# seeknobs5qtpy_22Feb2022.net
KiCad netlist of a schematic drawn in EAGLE
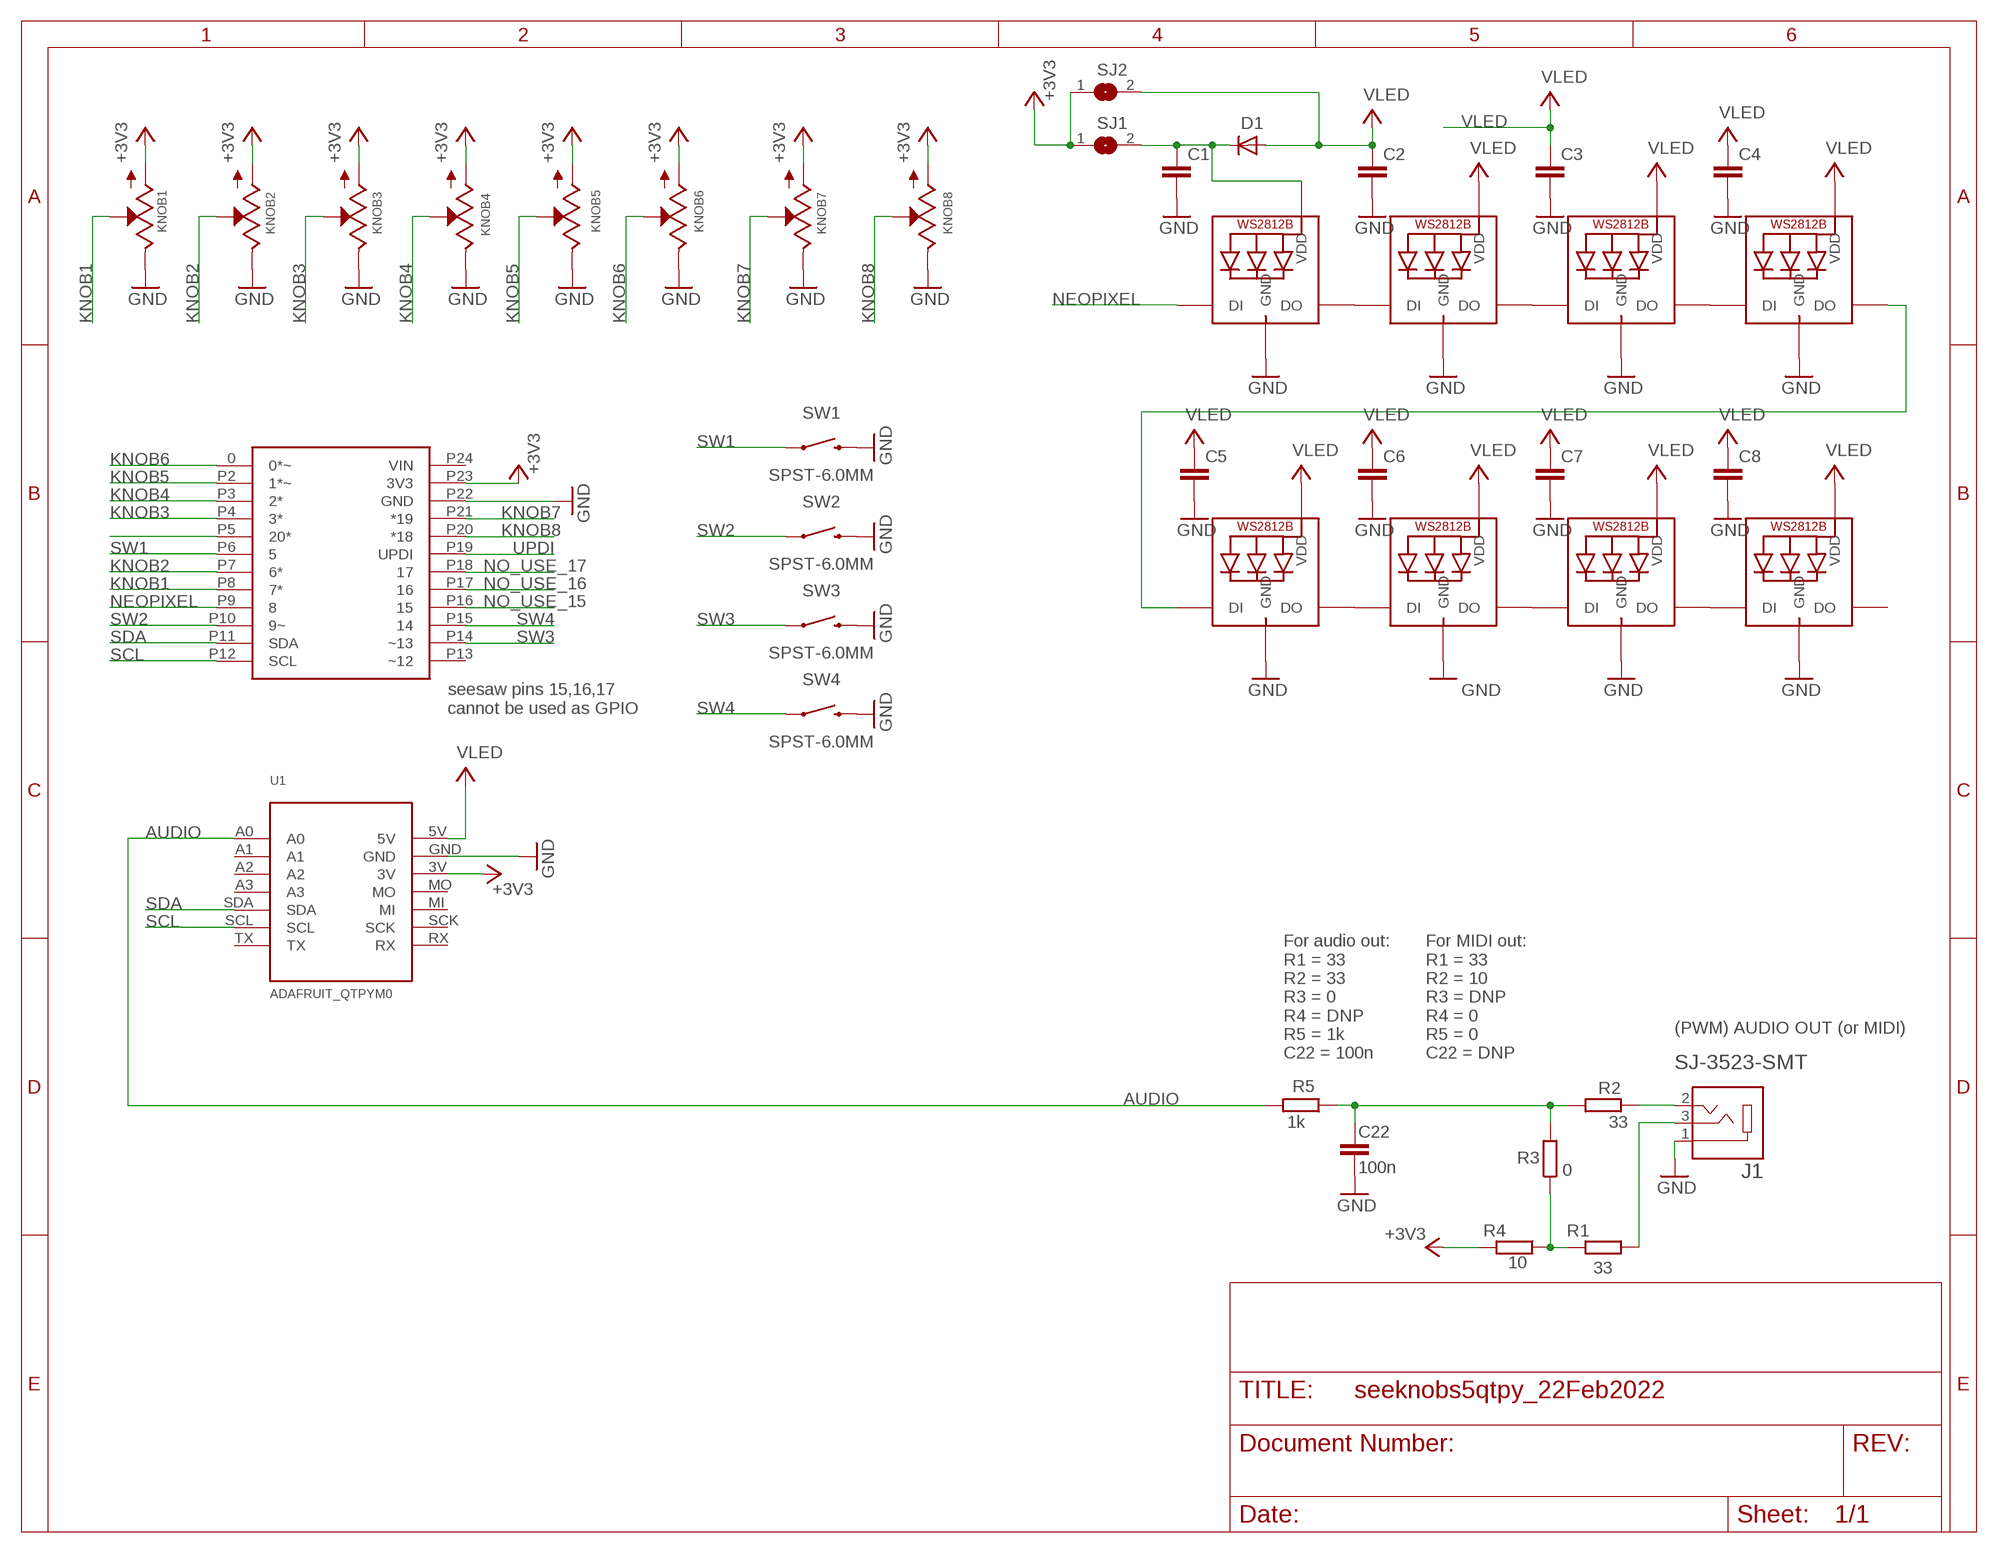
[diagram p0: schematic, sheet 1]

(export (version "E")
  (design (tool "Eeschema 10.0.6"))
  (components
    (comp (ref "C1")
      (value "C-EUC0805")
      (footprint "eagle-import:C0805")
      (libsource (lib "eagle-import") (part "C-EUC0805"))
    )
    (comp (ref "C2")
      (value "C-EUC0805")
      (footprint "eagle-import:C0805")
      (libsource (lib "eagle-import") (part "C-EUC0805"))
    )
    (comp (ref "C3")
      (value "C-EUC0805")
      (footprint "eagle-import:C0805")
      (libsource (lib "eagle-import") (part "C-EUC0805"))
    )
    (comp (ref "C4")
      (value "C-EUC0805")
      (footprint "eagle-import:C0805")
      (libsource (lib "eagle-import") (part "C-EUC0805"))
    )
    (comp (ref "C5")
      (value "C-EUC0805")
      (footprint "eagle-import:C0805")
      (libsource (lib "eagle-import") (part "C-EUC0805"))
    )
    (comp (ref "C6")
      (value "C-EUC0805")
      (footprint "eagle-import:C0805")
      (libsource (lib "eagle-import") (part "C-EUC0805"))
    )
    (comp (ref "C7")
      (value "C-EUC0805")
      (footprint "eagle-import:C0805")
      (libsource (lib "eagle-import") (part "C-EUC0805"))
    )
    (comp (ref "C8")
      (value "C-EUC0805")
      (footprint "eagle-import:C0805")
      (libsource (lib "eagle-import") (part "C-EUC0805"))
    )
    (comp (ref "C22")
      (value "100n")
      (footprint "eagle-import:C0805")
      (libsource (lib "eagle-import") (part "C-EUC0805"))
    )
    (comp (ref "D1")
      (value "DIODESOD-123")
      (footprint "eagle-import:SOD-123")
      (libsource (lib "eagle-import") (part "DIODESOD-123"))
    )
    (comp (ref "J1")
      (value "SJ-3523-SMT")
      (footprint "eagle-import:CUI_SJ-3523-SMT")
      (fields
        (field (name "DIGI-KEY_PART_NUMBER") "CP-3523SJCT-ND")
        (field (name "MF") "CUI Devices")
        (field (name "MP") "SJ-3523-SMT-TR")
      )
      (libsource (lib "eagle-import") (part "SJ-3523-SMT"))
    )
    (comp (ref "KNOB1")
      (value "POT")
      (footprint "eagle-import:ALPS_POT")
      (libsource (lib "eagle-import") (part "POT"))
    )
    (comp (ref "KNOB2")
      (value "POT")
      (footprint "eagle-import:ALPS_POT")
      (libsource (lib "eagle-import") (part "POT"))
    )
    (comp (ref "KNOB3")
      (value "POT")
      (footprint "eagle-import:ALPS_POT")
      (libsource (lib "eagle-import") (part "POT"))
    )
    (comp (ref "KNOB4")
      (value "POT")
      (footprint "eagle-import:ALPS_POT")
      (libsource (lib "eagle-import") (part "POT"))
    )
    (comp (ref "KNOB5")
      (value "POT")
      (footprint "eagle-import:ALPS_POT")
      (libsource (lib "eagle-import") (part "POT"))
    )
    (comp (ref "KNOB6")
      (value "POT")
      (footprint "eagle-import:ALPS_POT")
      (libsource (lib "eagle-import") (part "POT"))
    )
    (comp (ref "KNOB7")
      (value "POT")
      (footprint "eagle-import:ALPS_POT")
      (libsource (lib "eagle-import") (part "POT"))
    )
    (comp (ref "KNOB8")
      (value "POT")
      (footprint "eagle-import:ALPS_POT")
      (libsource (lib "eagle-import") (part "POT"))
    )
    (comp (ref "LED1")
      (value "MICROBUILDER_WS2812B_SK6812E")
      (footprint "eagle-import:MICROBUILDER_NEO3535_REVERSE")
      (libsource (lib "eagle-import") (part "MICROBUILDER_WS2812B_SK6812E"))
    )
    (comp (ref "LED2")
      (value "MICROBUILDER_WS2812B_SK6812E")
      (footprint "eagle-import:MICROBUILDER_NEO3535_REVERSE")
      (libsource (lib "eagle-import") (part "MICROBUILDER_WS2812B_SK6812E"))
    )
    (comp (ref "LED3")
      (value "MICROBUILDER_WS2812B_SK6812E")
      (footprint "eagle-import:MICROBUILDER_NEO3535_REVERSE")
      (libsource (lib "eagle-import") (part "MICROBUILDER_WS2812B_SK6812E"))
    )
    (comp (ref "LED4")
      (value "MICROBUILDER_WS2812B_SK6812E")
      (footprint "eagle-import:MICROBUILDER_NEO3535_REVERSE")
      (libsource (lib "eagle-import") (part "MICROBUILDER_WS2812B_SK6812E"))
    )
    (comp (ref "LED5")
      (value "MICROBUILDER_WS2812B_SK6812E")
      (footprint "eagle-import:MICROBUILDER_NEO3535_REVERSE")
      (libsource (lib "eagle-import") (part "MICROBUILDER_WS2812B_SK6812E"))
    )
    (comp (ref "LED6")
      (value "MICROBUILDER_WS2812B_SK6812E")
      (footprint "eagle-import:MICROBUILDER_NEO3535_REVERSE")
      (libsource (lib "eagle-import") (part "MICROBUILDER_WS2812B_SK6812E"))
    )
    (comp (ref "LED7")
      (value "MICROBUILDER_WS2812B_SK6812E")
      (footprint "eagle-import:MICROBUILDER_NEO3535_REVERSE")
      (libsource (lib "eagle-import") (part "MICROBUILDER_WS2812B_SK6812E"))
    )
    (comp (ref "LED8")
      (value "MICROBUILDER_WS2812B_SK6812E")
      (footprint "eagle-import:MICROBUILDER_NEO3535_REVERSE")
      (libsource (lib "eagle-import") (part "MICROBUILDER_WS2812B_SK6812E"))
    )
    (comp (ref "R1")
      (value "33")
      (footprint "eagle-import:R0805")
      (libsource (lib "eagle-import") (part "R-EU_R0805"))
    )
    (comp (ref "R2")
      (value "33")
      (footprint "eagle-import:R0805")
      (libsource (lib "eagle-import") (part "R-EU_R0805"))
    )
    (comp (ref "R3")
      (value "0")
      (footprint "eagle-import:R0805")
      (libsource (lib "eagle-import") (part "R-EU_R0805"))
    )
    (comp (ref "R4")
      (value "10")
      (footprint "eagle-import:R0805")
      (libsource (lib "eagle-import") (part "R-EU_R0805"))
    )
    (comp (ref "R5")
      (value "1k")
      (footprint "eagle-import:R0805")
      (libsource (lib "eagle-import") (part "R-EU_R0805"))
    )
    (comp (ref "SEESAW")
      (value "ADAFRUIT_SEESAW_ATTINY817")
      (footprint "eagle-import:ADAFRUIT_SEESAW_ATTINY817")
      (libsource (lib "eagle-import") (part "ADAFRUIT_SEESAW_ATTINY817"))
    )
    (comp (ref "SJ1") (value "SJ") (footprint "eagle-import:SJ") (libsource (lib "eagle-import") (part "SJ")))
    (comp (ref "SJ2") (value "SJ") (footprint "eagle-import:SJ") (libsource (lib "eagle-import") (part "SJ")))
    (comp (ref "SW1")
      (value "SPST-6.0MM")
      (footprint "eagle-import:TACTILE_SWITCH_PTH_6.0MM")
      (libsource (lib "eagle-import") (part "MOMENTARY-SWITCH-SPST-PTH-6.0MM"))
    )
    (comp (ref "SW2")
      (value "SPST-6.0MM")
      (footprint "eagle-import:TACTILE_SWITCH_PTH_6.0MM")
      (libsource (lib "eagle-import") (part "MOMENTARY-SWITCH-SPST-PTH-6.0MM"))
    )
    (comp (ref "SW3")
      (value "SPST-6.0MM")
      (footprint "eagle-import:TACTILE_SWITCH_PTH_6.0MM")
      (libsource (lib "eagle-import") (part "MOMENTARY-SWITCH-SPST-PTH-6.0MM"))
    )
    (comp (ref "SW4")
      (value "SPST-6.0MM")
      (footprint "eagle-import:TACTILE_SWITCH_PTH_6.0MM")
      (libsource (lib "eagle-import") (part "MOMENTARY-SWITCH-SPST-PTH-6.0MM"))
    )
    (comp (ref "U1")
      (value "ADAFRUIT_QTPYM0")
      (footprint "eagle-import:ADAFRUIT_QTPY_M0")
      (libsource (lib "eagle-import") (part "ADAFRUIT_QTPYM0"))
    )
  )
  (nets
    (net (code "1") (name "+3V3") (class "Default")
      (node (ref "KNOB1") (pin "P$3") (pinfunction "A_P$3") (pintype "passive"))
      (node (ref "KNOB2") (pin "P$3") (pinfunction "A_P$3") (pintype "passive"))
      (node (ref "KNOB3") (pin "P$3") (pinfunction "A_P$3") (pintype "passive"))
      (node (ref "KNOB4") (pin "P$3") (pinfunction "A_P$3") (pintype "passive"))
      (node (ref "KNOB5") (pin "P$3") (pinfunction "A_P$3") (pintype "passive"))
      (node (ref "KNOB6") (pin "P$3") (pinfunction "A_P$3") (pintype "passive"))
      (node (ref "KNOB7") (pin "P$3") (pinfunction "A_P$3") (pintype "passive"))
      (node (ref "KNOB8") (pin "P$3") (pinfunction "A_P$3") (pintype "passive"))
      (node (ref "R4") (pin "2") (pinfunction "2_2") (pintype "passive"))
      (node (ref "SEESAW") (pin "P23") (pinfunction "3V3_P23") (pintype "bidirectional"))
      (node (ref "SJ1") (pin "1") (pinfunction "1_1") (pintype "passive"))
      (node (ref "SJ2") (pin "1") (pinfunction "1_1") (pintype "passive"))
      (node (ref "U1") (pin "3V") (pinfunction "3V_3V") (pintype "bidirectional"))
    )
    (net (code "2") (name "/AUDIO") (class "Default")
      (node (ref "R5") (pin "2") (pinfunction "2_2") (pintype "passive"))
      (node (ref "U1") (pin "A0") (pinfunction "A0_A0") (pintype "bidirectional"))
    )
    (net (code "3") (name "/KNOB1") (class "Default")
      (node (ref "KNOB1") (pin "P$2") (pinfunction "S_P$2") (pintype "passive"))
      (node (ref "SEESAW") (pin "P8") (pinfunction "7*_P8") (pintype "bidirectional"))
    )
    (net (code "4") (name "/KNOB2") (class "Default")
      (node (ref "KNOB2") (pin "P$2") (pinfunction "S_P$2") (pintype "passive"))
      (node (ref "SEESAW") (pin "P7") (pinfunction "6*_P7") (pintype "bidirectional"))
    )
    (net (code "5") (name "/KNOB3") (class "Default")
      (node (ref "KNOB3") (pin "P$2") (pinfunction "S_P$2") (pintype "passive"))
      (node (ref "SEESAW") (pin "P4") (pinfunction "3*_P4") (pintype "bidirectional"))
    )
    (net (code "6") (name "/KNOB4") (class "Default")
      (node (ref "KNOB4") (pin "P$2") (pinfunction "S_P$2") (pintype "passive"))
      (node (ref "SEESAW") (pin "P3") (pinfunction "2*_P3") (pintype "bidirectional"))
    )
    (net (code "7") (name "/KNOB5") (class "Default")
      (node (ref "KNOB5") (pin "P$2") (pinfunction "S_P$2") (pintype "passive"))
      (node (ref "SEESAW") (pin "P2") (pinfunction "1*~{}_P2") (pintype "bidirectional"))
    )
    (net (code "8") (name "/KNOB6") (class "Default")
      (node (ref "KNOB6") (pin "P$2") (pinfunction "S_P$2") (pintype "passive"))
      (node (ref "SEESAW") (pin "0") (pinfunction "0*~{}_0") (pintype "bidirectional"))
    )
    (net (code "9") (name "/KNOB7") (class "Default")
      (node (ref "KNOB7") (pin "P$2") (pinfunction "S_P$2") (pintype "passive"))
      (node (ref "SEESAW") (pin "P21") (pinfunction "*19_P21") (pintype "bidirectional"))
    )
    (net (code "10") (name "/KNOB8") (class "Default")
      (node (ref "KNOB8") (pin "P$2") (pinfunction "S_P$2") (pintype "passive"))
      (node (ref "SEESAW") (pin "P20") (pinfunction "*18_P20") (pintype "bidirectional"))
    )
    (net (code "11") (name "/NEOPIXEL") (class "Default")
      (node (ref "LED1") (pin "4-DIN") (pinfunction "DI_4-DIN") (pintype "input"))
      (node (ref "SEESAW") (pin "P9") (pinfunction "8_P9") (pintype "bidirectional"))
    )
    (net (code "12") (name "/NO_USE_15") (class "Default")
      (node (ref "SEESAW") (pin "P16") (pinfunction "15_P16") (pintype "bidirectional"))
    )
    (net (code "13") (name "/NO_USE_16") (class "Default")
      (node (ref "SEESAW") (pin "P17") (pinfunction "16_P17") (pintype "bidirectional"))
    )
    (net (code "14") (name "/NO_USE_17") (class "Default")
      (node (ref "SEESAW") (pin "P18") (pinfunction "17_P18") (pintype "bidirectional"))
    )
    (net (code "15") (name "/SCL") (class "Default")
      (node (ref "SEESAW") (pin "P12") (pinfunction "SCL_P12") (pintype "bidirectional"))
      (node (ref "U1") (pin "SCL") (pinfunction "SCL_SCL") (pintype "bidirectional"))
    )
    (net (code "16") (name "/SDA") (class "Default")
      (node (ref "SEESAW") (pin "P11") (pinfunction "SDA_P11") (pintype "bidirectional"))
      (node (ref "U1") (pin "SDA") (pinfunction "SDA_SDA") (pintype "bidirectional"))
    )
    (net (code "17") (name "/SW1") (class "Default")
      (node (ref "SEESAW") (pin "P6") (pinfunction "5_P6") (pintype "bidirectional"))
      (node (ref "SW1") (pin "1") (pinfunction "1_1") (pintype "passive"))
    )
    (net (code "18") (name "/SW2") (class "Default")
      (node (ref "SEESAW") (pin "P10") (pinfunction "9~{}_P10") (pintype "bidirectional"))
      (node (ref "SW2") (pin "1") (pinfunction "1_1") (pintype "passive"))
    )
    (net (code "19") (name "/SW3") (class "Default")
      (node (ref "SEESAW") (pin "P14") (pinfunction "~{13}_P14") (pintype "bidirectional"))
      (node (ref "SW3") (pin "1") (pinfunction "1_1") (pintype "passive"))
    )
    (net (code "20") (name "/SW4") (class "Default")
      (node (ref "SEESAW") (pin "P15") (pinfunction "14_P15") (pintype "bidirectional"))
      (node (ref "SW4") (pin "1") (pinfunction "1_1") (pintype "passive"))
    )
    (net (code "21") (name "/UPDI") (class "Default")
      (node (ref "SEESAW") (pin "P19") (pinfunction "UPDI_P19") (pintype "bidirectional"))
    )
    (net (code "22") (name "GND") (class "Default")
      (node (ref "C1") (pin "2") (pinfunction "2_2") (pintype "passive"))
      (node (ref "C2") (pin "2") (pinfunction "2_2") (pintype "passive"))
      (node (ref "C22") (pin "2") (pinfunction "2_2") (pintype "passive"))
      (node (ref "C3") (pin "2") (pinfunction "2_2") (pintype "passive"))
      (node (ref "C4") (pin "2") (pinfunction "2_2") (pintype "passive"))
      (node (ref "C5") (pin "2") (pinfunction "2_2") (pintype "passive"))
      (node (ref "C6") (pin "2") (pinfunction "2_2") (pintype "passive"))
      (node (ref "C7") (pin "2") (pinfunction "2_2") (pintype "passive"))
      (node (ref "C8") (pin "2") (pinfunction "2_2") (pintype "passive"))
      (node (ref "J1") (pin "1") (pinfunction "1_1") (pintype "passive"))
      (node (ref "KNOB1") (pin "P$1") (pinfunction "E_P$1") (pintype "passive"))
      (node (ref "KNOB2") (pin "P$1") (pinfunction "E_P$1") (pintype "passive"))
      (node (ref "KNOB3") (pin "P$1") (pinfunction "E_P$1") (pintype "passive"))
      (node (ref "KNOB4") (pin "P$1") (pinfunction "E_P$1") (pintype "passive"))
      (node (ref "KNOB5") (pin "P$1") (pinfunction "E_P$1") (pintype "passive"))
      (node (ref "KNOB6") (pin "P$1") (pinfunction "E_P$1") (pintype "passive"))
      (node (ref "KNOB7") (pin "P$1") (pinfunction "E_P$1") (pintype "passive"))
      (node (ref "KNOB8") (pin "P$1") (pinfunction "E_P$1") (pintype "passive"))
      (node (ref "LED1") (pin "3-GND") (pinfunction "GND_3-GND") (pintype "power_in"))
      (node (ref "LED2") (pin "3-GND") (pinfunction "GND_3-GND") (pintype "power_in"))
      (node (ref "LED3") (pin "3-GND") (pinfunction "GND_3-GND") (pintype "power_in"))
      (node (ref "LED4") (pin "3-GND") (pinfunction "GND_3-GND") (pintype "power_in"))
      (node (ref "LED5") (pin "3-GND") (pinfunction "GND_3-GND") (pintype "power_in"))
      (node (ref "LED6") (pin "3-GND") (pinfunction "GND_3-GND") (pintype "power_in"))
      (node (ref "LED7") (pin "3-GND") (pinfunction "GND_3-GND") (pintype "power_in"))
      (node (ref "LED8") (pin "3-GND") (pinfunction "GND_3-GND") (pintype "power_in"))
      (node (ref "SEESAW") (pin "P22") (pinfunction "GND_P22") (pintype "bidirectional"))
      (node (ref "SW1") (pin "3") (pinfunction "2_3") (pintype "passive"))
      (node (ref "SW2") (pin "3") (pinfunction "2_3") (pintype "passive"))
      (node (ref "SW3") (pin "3") (pinfunction "2_3") (pintype "passive"))
      (node (ref "SW4") (pin "3") (pinfunction "2_3") (pintype "passive"))
      (node (ref "U1") (pin "GND") (pinfunction "GND_GND") (pintype "bidirectional"))
    )
    (net (code "23") (name "Net-(C22-Pad1)") (class "Default")
      (node (ref "C22") (pin "1") (pinfunction "1_1") (pintype "passive"))
      (node (ref "R2") (pin "2") (pinfunction "2_2") (pintype "passive"))
      (node (ref "R3") (pin "2") (pinfunction "2_2") (pintype "passive"))
      (node (ref "R5") (pin "1") (pinfunction "1_1") (pintype "passive"))
    )
    (net (code "24") (name "Net-(J1-Pad2)") (class "Default")
      (node (ref "J1") (pin "2") (pinfunction "2_2") (pintype "passive"))
      (node (ref "R2") (pin "1") (pinfunction "1_1") (pintype "passive"))
    )
    (net (code "25") (name "Net-(J1-Pad3)") (class "Default")
      (node (ref "J1") (pin "3") (pinfunction "3_3") (pintype "passive"))
      (node (ref "R1") (pin "1") (pinfunction "1_1") (pintype "passive"))
    )
    (net (code "26") (name "Net-(LED1-DO)") (class "Default")
      (node (ref "LED1") (pin "2-DOUT") (pinfunction "DO_2-DOUT") (pintype "output"))
      (node (ref "LED2") (pin "4-DIN") (pinfunction "DI_4-DIN") (pintype "input"))
    )
    (net (code "27") (name "Net-(LED1-VDD)") (class "Default")
      (node (ref "C1") (pin "1") (pinfunction "1_1") (pintype "passive"))
      (node (ref "D1") (pin "C") (pinfunction "C_C") (pintype "passive"))
      (node (ref "LED1") (pin "1-VDD") (pinfunction "VDD_1-VDD") (pintype "power_in"))
      (node (ref "SJ1") (pin "2") (pinfunction "2_2") (pintype "passive"))
    )
    (net (code "28") (name "Net-(LED2-DO)") (class "Default")
      (node (ref "LED2") (pin "2-DOUT") (pinfunction "DO_2-DOUT") (pintype "output"))
      (node (ref "LED3") (pin "4-DIN") (pinfunction "DI_4-DIN") (pintype "input"))
    )
    (net (code "29") (name "Net-(LED3-DO)") (class "Default")
      (node (ref "LED3") (pin "2-DOUT") (pinfunction "DO_2-DOUT") (pintype "output"))
      (node (ref "LED4") (pin "4-DIN") (pinfunction "DI_4-DIN") (pintype "input"))
    )
    (net (code "30") (name "Net-(LED4-DO)") (class "Default")
      (node (ref "LED4") (pin "2-DOUT") (pinfunction "DO_2-DOUT") (pintype "output"))
      (node (ref "LED5") (pin "4-DIN") (pinfunction "DI_4-DIN") (pintype "input"))
    )
    (net (code "31") (name "Net-(LED5-DO)") (class "Default")
      (node (ref "LED5") (pin "2-DOUT") (pinfunction "DO_2-DOUT") (pintype "output"))
      (node (ref "LED6") (pin "4-DIN") (pinfunction "DI_4-DIN") (pintype "input"))
    )
    (net (code "32") (name "Net-(LED6-DO)") (class "Default")
      (node (ref "LED6") (pin "2-DOUT") (pinfunction "DO_2-DOUT") (pintype "output"))
      (node (ref "LED7") (pin "4-DIN") (pinfunction "DI_4-DIN") (pintype "input"))
    )
    (net (code "33") (name "Net-(LED7-DO)") (class "Default")
      (node (ref "LED7") (pin "2-DOUT") (pinfunction "DO_2-DOUT") (pintype "output"))
      (node (ref "LED8") (pin "4-DIN") (pinfunction "DI_4-DIN") (pintype "input"))
    )
    (net (code "34") (name "Net-(R1-Pad2)") (class "Default")
      (node (ref "R1") (pin "2") (pinfunction "2_2") (pintype "passive"))
      (node (ref "R3") (pin "1") (pinfunction "1_1") (pintype "passive"))
      (node (ref "R4") (pin "1") (pinfunction "1_1") (pintype "passive"))
    )
    (net (code "35") (name "VLED") (class "Default")
      (node (ref "C2") (pin "1") (pinfunction "1_1") (pintype "passive"))
      (node (ref "C3") (pin "1") (pinfunction "1_1") (pintype "passive"))
      (node (ref "C4") (pin "1") (pinfunction "1_1") (pintype "passive"))
      (node (ref "C5") (pin "1") (pinfunction "1_1") (pintype "passive"))
      (node (ref "C6") (pin "1") (pinfunction "1_1") (pintype "passive"))
      (node (ref "C7") (pin "1") (pinfunction "1_1") (pintype "passive"))
      (node (ref "C8") (pin "1") (pinfunction "1_1") (pintype "passive"))
      (node (ref "D1") (pin "A") (pinfunction "A_A") (pintype "passive"))
      (node (ref "LED2") (pin "1-VDD") (pinfunction "VDD_1-VDD") (pintype "power_in"))
      (node (ref "LED3") (pin "1-VDD") (pinfunction "VDD_1-VDD") (pintype "power_in"))
      (node (ref "LED4") (pin "1-VDD") (pinfunction "VDD_1-VDD") (pintype "power_in"))
      (node (ref "LED5") (pin "1-VDD") (pinfunction "VDD_1-VDD") (pintype "power_in"))
      (node (ref "LED6") (pin "1-VDD") (pinfunction "VDD_1-VDD") (pintype "power_in"))
      (node (ref "LED7") (pin "1-VDD") (pinfunction "VDD_1-VDD") (pintype "power_in"))
      (node (ref "LED8") (pin "1-VDD") (pinfunction "VDD_1-VDD") (pintype "power_in"))
      (node (ref "SJ2") (pin "2") (pinfunction "2_2") (pintype "passive"))
      (node (ref "U1") (pin "5V") (pinfunction "5V_5V") (pintype "bidirectional"))
    )
    (net (code "36") (name "unconnected-(LED8-DO-Pad2-DOUT)") (class "Default")
      (node (ref "LED8") (pin "2-DOUT") (pinfunction "DO_2-DOUT") (pintype "output"))
    )
    (net (code "37") (name "unconnected-(SEESAW-20*-PadP5)") (class "Default")
      (node (ref "SEESAW") (pin "P5") (pinfunction "20*_P5") (pintype "bidirectional"))
    )
    (net (code "38") (name "unconnected-(SEESAW-VIN-PadP24)") (class "Default")
      (node (ref "SEESAW") (pin "P24") (pinfunction "VIN_P24") (pintype "bidirectional"))
    )
    (net (code "39") (name "unconnected-(SEESAW-~{12}-PadP13)") (class "Default")
      (node (ref "SEESAW") (pin "P13") (pinfunction "~{12}_P13") (pintype "bidirectional"))
    )
    (net (code "40") (name "unconnected-(U1-PadA1)") (class "Default")
      (node (ref "U1") (pin "A1") (pinfunction "A1_A1") (pintype "bidirectional"))
    )
    (net (code "41") (name "unconnected-(U1-PadA2)") (class "Default")
      (node (ref "U1") (pin "A2") (pinfunction "A2_A2") (pintype "bidirectional"))
    )
    (net (code "42") (name "unconnected-(U1-PadA3)") (class "Default")
      (node (ref "U1") (pin "A3") (pinfunction "A3_A3") (pintype "bidirectional"))
    )
    (net (code "43") (name "unconnected-(U1-PadMI)") (class "Default")
      (node (ref "U1") (pin "MI") (pinfunction "MI_MI") (pintype "bidirectional"))
    )
    (net (code "44") (name "unconnected-(U1-PadMO)") (class "Default")
      (node (ref "U1") (pin "MO") (pinfunction "MO_MO") (pintype "bidirectional"))
    )
    (net (code "45") (name "unconnected-(U1-PadRX)") (class "Default")
      (node (ref "U1") (pin "RX") (pinfunction "RX_RX") (pintype "bidirectional"))
    )
    (net (code "46") (name "unconnected-(U1-PadSCK)") (class "Default")
      (node (ref "U1") (pin "SCK") (pinfunction "SCK_SCK") (pintype "bidirectional"))
    )
    (net (code "47") (name "unconnected-(U1-PadTX)") (class "Default")
      (node (ref "U1") (pin "TX") (pinfunction "TX_TX") (pintype "bidirectional"))
    )
  )
)
